# Generador_de_Funciones_v2.net
KiCad netlist of a schematic drawn in EAGLE
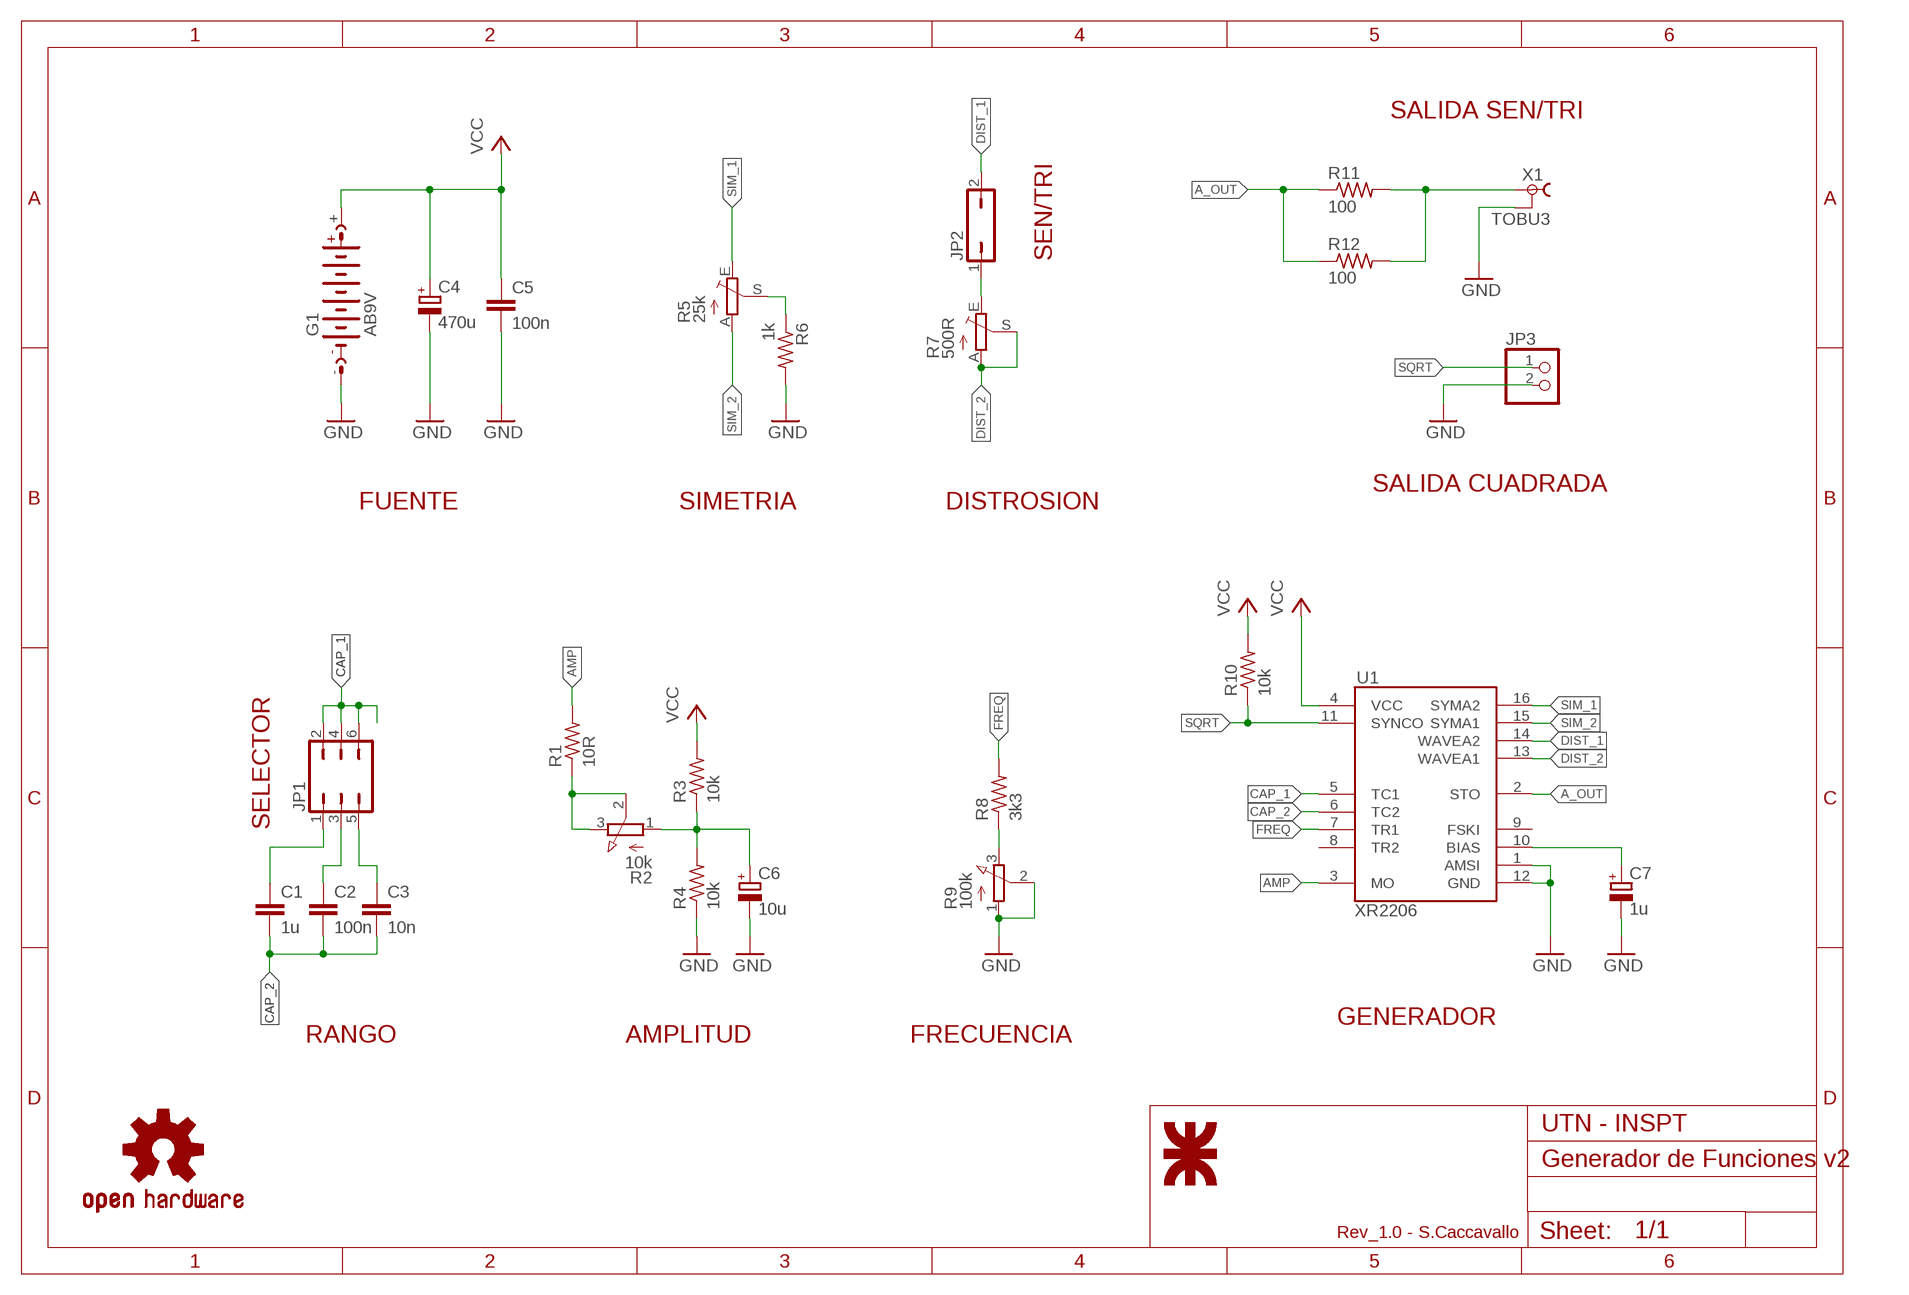
[diagram p0: schematic, sheet 1]

(export (version "E")
  (design (tool "Eeschema 10.0.6"))
  (components
    (comp (ref "C1")
      (value "1u")
      (footprint "eagle-import:C050-024X044")
      (libsource (lib "eagle-import") (part "C-EU050-024X044"))
    )
    (comp (ref "C2")
      (value "100n")
      (footprint "eagle-import:C050-024X044")
      (libsource (lib "eagle-import") (part "C-EU050-024X044"))
    )
    (comp (ref "C3")
      (value "10n")
      (footprint "eagle-import:C050-024X044")
      (libsource (lib "eagle-import") (part "C-EU050-024X044"))
    )
    (comp (ref "C4")
      (value "470u")
      (footprint "eagle-import:E3,5-8")
      (libsource (lib "eagle-import") (part "CPOL-EUE3.5-8"))
    )
    (comp (ref "C5")
      (value "100n")
      (footprint "eagle-import:C050-024X044")
      (libsource (lib "eagle-import") (part "C-EU050-024X044"))
    )
    (comp (ref "C6")
      (value "10u")
      (footprint "eagle-import:E2,5-6")
      (libsource (lib "eagle-import") (part "CPOL-EUE2.5-6"))
    )
    (comp (ref "C7")
      (value "1u")
      (footprint "eagle-import:E2,5-6")
      (libsource (lib "eagle-import") (part "CPOL-EUE2.5-6"))
    )
    (comp (ref "G1")
      (value "AB9V")
      (footprint "eagle-import:AB9V")
      (libsource (lib "eagle-import") (part "AB9V"))
    )
    (comp (ref "JP1")
      (value "JP3Q")
      (footprint "eagle-import:JP3Q")
      (libsource (lib "eagle-import") (part "JP3Q"))
    )
    (comp (ref "JP2")
      (value "JP1Q")
      (footprint "eagle-import:JP1")
      (libsource (lib "eagle-import") (part "JP1Q"))
    )
    (comp (ref "JP3")
      (value "PINHD-1X2")
      (footprint "eagle-import:1X02")
      (libsource (lib "eagle-import") (part "PINHD-1X2"))
    )
    (comp (ref "R1")
      (value "10R")
      (footprint "eagle-import:0207_10")
      (libsource (lib "eagle-import") (part "R-US_0207/10"))
    )
    (comp (ref "R2")
      (value "10k")
      (footprint "eagle-import:3RP_1610N")
      (libsource (lib "eagle-import") (part "3RP/1610N"))
    )
    (comp (ref "R3")
      (value "10k")
      (footprint "eagle-import:0207_10")
      (libsource (lib "eagle-import") (part "R-US_0207/10"))
    )
    (comp (ref "R4")
      (value "10k")
      (footprint "eagle-import:0207_10")
      (libsource (lib "eagle-import") (part "R-US_0207/10"))
    )
    (comp (ref "R5")
      (value "25k")
      (footprint "eagle-import:RJ9W")
      (libsource (lib "eagle-import") (part "TRIM_EU-RJ9W"))
    )
    (comp (ref "R6")
      (value "1k")
      (footprint "eagle-import:0207_10")
      (libsource (lib "eagle-import") (part "R-US_0207/10"))
    )
    (comp (ref "R7")
      (value "500R")
      (footprint "eagle-import:RJ9W")
      (libsource (lib "eagle-import") (part "TRIM_EU-RJ9W"))
    )
    (comp (ref "R8")
      (value "3k3")
      (footprint "eagle-import:0207_10")
      (libsource (lib "eagle-import") (part "R-US_0207/10"))
    )
    (comp (ref "R9")
      (value "100k")
      (footprint "eagle-import:3RP_1610N")
      (libsource (lib "eagle-import") (part "3RP/1610N"))
    )
    (comp (ref "R10")
      (value "10k")
      (footprint "eagle-import:0207_10")
      (libsource (lib "eagle-import") (part "R-US_0207/10"))
    )
    (comp (ref "R11")
      (value "100")
      (footprint "eagle-import:0207_10")
      (libsource (lib "eagle-import") (part "R-US_0207/10"))
    )
    (comp (ref "R12")
      (value "100")
      (footprint "eagle-import:0207_10")
      (libsource (lib "eagle-import") (part "R-US_0207/10"))
    )
    (comp (ref "U$1")
      (value "UTN_LOGO_0")
      (footprint "eagle-import:UTN_LOGO_0_TOP")
      (libsource (lib "eagle-import") (part "UTN_LOGO_0"))
    )
    (comp (ref "U$4")
      (value "OSHW-LOGOM")
      (footprint "eagle-import:OSHW-LOGO-M")
      (libsource (lib "eagle-import") (part "OSHW-LOGOM"))
    )
    (comp (ref "U1")
      (value "XR2206")
      (footprint "eagle-import:DIL16")
      (libsource (lib "eagle-import") (part "XR2206"))
    )
    (comp (ref "X1")
      (value "TOBU3")
      (footprint "eagle-import:TOBU3")
      (fields (field (name "MF") "FARNELL") (field (name "MPN") "TOBU 3"))
      (libsource (lib "eagle-import") (part "TOBU3"))
    )
  )
  (nets
    (net (code "1") (name "AMP") (class "Default")
      (node (ref "R1") (pin "2") (pinfunction "2_2") (pintype "passive"))
      (node (ref "U1") (pin "3") (pinfunction "MO_3") (pintype "output"))
    )
    (net (code "2") (name "A_OUT") (class "Default")
      (node (ref "R11") (pin "1") (pinfunction "1_1") (pintype "passive"))
      (node (ref "R12") (pin "1") (pinfunction "1_1") (pintype "passive"))
      (node (ref "U1") (pin "2") (pinfunction "STO_2") (pintype "output"))
    )
    (net (code "3") (name "CAP_1") (class "Default")
      (node (ref "JP1") (pin "2") (pinfunction "2_2") (pintype "passive"))
      (node (ref "JP1") (pin "4") (pinfunction "4_4") (pintype "passive"))
      (node (ref "JP1") (pin "6") (pinfunction "6_6") (pintype "passive"))
      (node (ref "U1") (pin "5") (pinfunction "TC1_5") (pintype "input"))
    )
    (net (code "4") (name "CAP_2") (class "Default")
      (node (ref "C1") (pin "2") (pinfunction "2_2") (pintype "passive"))
      (node (ref "C2") (pin "2") (pinfunction "2_2") (pintype "passive"))
      (node (ref "C3") (pin "2") (pinfunction "2_2") (pintype "passive"))
      (node (ref "U1") (pin "6") (pinfunction "TC2_6") (pintype "input"))
    )
    (net (code "5") (name "DIST_1") (class "Default")
      (node (ref "JP2") (pin "2") (pinfunction "2_2") (pintype "passive"))
      (node (ref "U1") (pin "14") (pinfunction "WAVEA2_14") (pintype "input"))
    )
    (net (code "6") (name "DIST_2") (class "Default")
      (node (ref "R7") (pin "A") (pinfunction "A_A") (pintype "passive"))
      (node (ref "R7") (pin "S") (pinfunction "S_S") (pintype "passive"))
      (node (ref "U1") (pin "13") (pinfunction "WAVEA1_13") (pintype "input"))
    )
    (net (code "7") (name "FREQ") (class "Default")
      (node (ref "R8") (pin "2") (pinfunction "2_2") (pintype "passive"))
      (node (ref "U1") (pin "7") (pinfunction "TR1_7") (pintype "output"))
    )
    (net (code "8") (name "GND") (class "Default")
      (node (ref "C4") (pin "-") (pinfunction "-_-") (pintype "passive"))
      (node (ref "C5") (pin "2") (pinfunction "2_2") (pintype "passive"))
      (node (ref "C6") (pin "-") (pinfunction "-_-") (pintype "passive"))
      (node (ref "C7") (pin "-") (pinfunction "-_-") (pintype "passive"))
      (node (ref "G1") (pin "-") (pinfunction "-_-") (pintype "passive"))
      (node (ref "JP3") (pin "2") (pinfunction "2_2") (pintype "passive"))
      (node (ref "R4") (pin "1") (pinfunction "1_1") (pintype "passive"))
      (node (ref "R6") (pin "2") (pinfunction "2_2") (pintype "passive"))
      (node (ref "R9") (pin "1") (pinfunction "A_1") (pintype "passive"))
      (node (ref "R9") (pin "2") (pinfunction "S_2") (pintype "passive"))
      (node (ref "U1") (pin "1") (pinfunction "AMSI_1") (pintype "input"))
      (node (ref "U1") (pin "12") (pinfunction "GND_12") (pintype "power_in"))
      (node (ref "X1") (pin "2") (pinfunction "2_2") (pintype "passive"))
      (node (ref "X1") (pin "2@1") (pinfunction "2_2@1") (pintype "passive"))
      (node (ref "X1") (pin "2@2") (pinfunction "2_2@2") (pintype "passive"))
    )
    (net (code "9") (name "Net-(C1-Pad1)") (class "Default")
      (node (ref "C1") (pin "1") (pinfunction "1_1") (pintype "passive"))
      (node (ref "JP1") (pin "1") (pinfunction "1_1") (pintype "passive"))
    )
    (net (code "10") (name "Net-(C2-Pad1)") (class "Default")
      (node (ref "C2") (pin "1") (pinfunction "1_1") (pintype "passive"))
      (node (ref "JP1") (pin "3") (pinfunction "3_3") (pintype "passive"))
    )
    (net (code "11") (name "Net-(C3-Pad1)") (class "Default")
      (node (ref "C3") (pin "1") (pinfunction "1_1") (pintype "passive"))
      (node (ref "JP1") (pin "5") (pinfunction "5_5") (pintype "passive"))
    )
    (net (code "12") (name "Net-(JP2-Pad1)") (class "Default")
      (node (ref "JP2") (pin "1") (pinfunction "1_1") (pintype "passive"))
      (node (ref "R7") (pin "E") (pinfunction "E_E") (pintype "passive"))
    )
    (net (code "13") (name "Net-(R2-A)") (class "Default")
      (node (ref "C6") (pin "+") (pinfunction "+_+") (pintype "passive"))
      (node (ref "R2") (pin "1") (pinfunction "A_1") (pintype "passive"))
      (node (ref "R3") (pin "1") (pinfunction "1_1") (pintype "passive"))
      (node (ref "R4") (pin "2") (pinfunction "2_2") (pintype "passive"))
    )
    (net (code "14") (name "Net-(R2-E)") (class "Default")
      (node (ref "R1") (pin "1") (pinfunction "1_1") (pintype "passive"))
      (node (ref "R2") (pin "2") (pinfunction "S_2") (pintype "passive"))
      (node (ref "R2") (pin "3") (pinfunction "E_3") (pintype "passive"))
    )
    (net (code "15") (name "Net-(R5-PadS)") (class "Default")
      (node (ref "R5") (pin "S") (pinfunction "S_S") (pintype "passive"))
      (node (ref "R6") (pin "1") (pinfunction "1_1") (pintype "passive"))
    )
    (net (code "16") (name "Net-(R9-E)") (class "Default")
      (node (ref "R8") (pin "1") (pinfunction "1_1") (pintype "passive"))
      (node (ref "R9") (pin "3") (pinfunction "E_3") (pintype "passive"))
    )
    (net (code "17") (name "Net-(R11-Pad2)") (class "Default")
      (node (ref "R11") (pin "2") (pinfunction "2_2") (pintype "passive"))
      (node (ref "R12") (pin "2") (pinfunction "2_2") (pintype "passive"))
      (node (ref "X1") (pin "1") (pinfunction "1_1") (pintype "passive"))
    )
    (net (code "18") (name "Net-(U1-BIAS)") (class "Default")
      (node (ref "C7") (pin "+") (pinfunction "+_+") (pintype "passive"))
      (node (ref "U1") (pin "10") (pinfunction "BIAS_10") (pintype "output"))
    )
    (net (code "19") (name "SIM_1") (class "Default")
      (node (ref "R5") (pin "E") (pinfunction "E_E") (pintype "passive"))
      (node (ref "U1") (pin "16") (pinfunction "SYMA2_16") (pintype "input"))
    )
    (net (code "20") (name "SIM_2") (class "Default")
      (node (ref "R5") (pin "A") (pinfunction "A_A") (pintype "passive"))
      (node (ref "U1") (pin "15") (pinfunction "SYMA1_15") (pintype "input"))
    )
    (net (code "21") (name "SQRT") (class "Default")
      (node (ref "JP3") (pin "1") (pinfunction "1_1") (pintype "passive"))
      (node (ref "R10") (pin "1") (pinfunction "1_1") (pintype "passive"))
      (node (ref "U1") (pin "11") (pinfunction "SYNCO_11") (pintype "output"))
    )
    (net (code "22") (name "VCC") (class "Default")
      (node (ref "C4") (pin "+") (pinfunction "+_+") (pintype "passive"))
      (node (ref "C5") (pin "1") (pinfunction "1_1") (pintype "passive"))
      (node (ref "G1") (pin "+") (pinfunction "+_+") (pintype "passive"))
      (node (ref "R10") (pin "2") (pinfunction "2_2") (pintype "passive"))
      (node (ref "R3") (pin "2") (pinfunction "2_2") (pintype "passive"))
      (node (ref "U1") (pin "4") (pinfunction "VCC_4") (pintype "power_in"))
    )
    (net (code "23") (name "unconnected-(U1-FSKI-Pad9)") (class "Default")
      (node (ref "U1") (pin "9") (pinfunction "FSKI_9") (pintype "input"))
    )
    (net (code "24") (name "unconnected-(U1-TR2-Pad8)") (class "Default")
      (node (ref "U1") (pin "8") (pinfunction "TR2_8") (pintype "output"))
    )
  )
)
